# MEMORY.net
KiCad netlist of a schematic drawn in Altium Designer
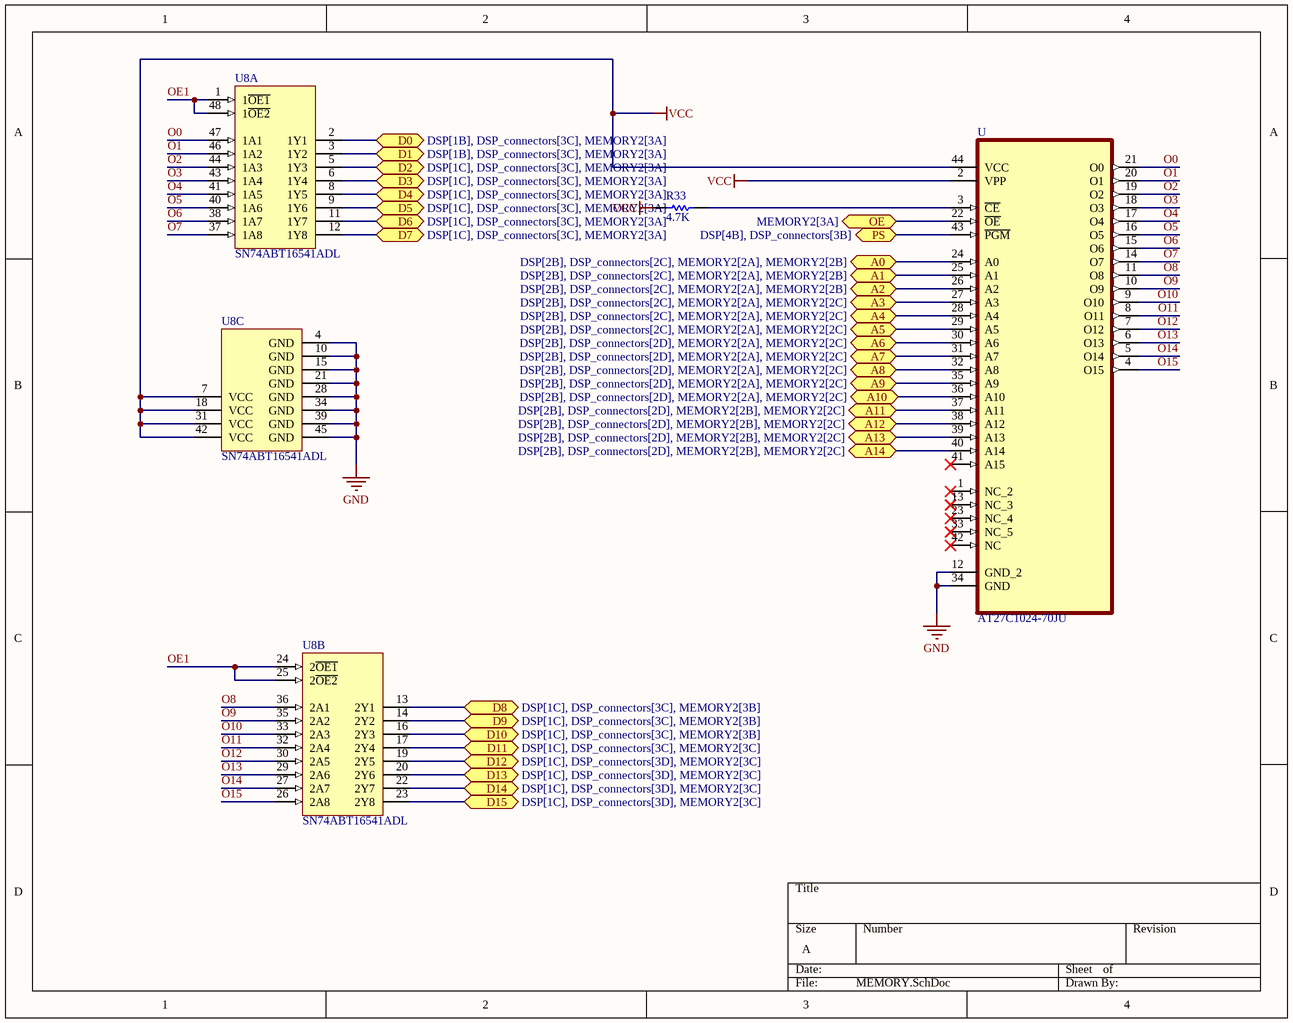
[diagram p0: MEMORY.SchDoc]

(export (version "E")
  (design (tool "Eeschema 10.0.6"))
  (components
    (comp (ref "R33")
      (value "4.7K")
      (footprint "RESC2013X60X35ML10T20")
      (fields (field (name "TOLERANCE") "5%") (field (name "MANUFACTURER") "Yageo"))
      (libsource (lib "Altium Content Vault") (part "RES-2"))
    )
    (comp (ref "U")
      (value "AT27C1024-70JU")
      (footprint "PLCC127P1752X1752X457-44N")
      (description "EPROM - OTP Memory IC 1Mb _64K x 16_ Parallel 70ns 44-PLCC _16.6x16.6_")
      (fields (field (name "MF") "Microchip"))
      (libsource (lib "AT27C1024-70JU") (part "AT27C1024-70JU"))
    )
    (comp (ref "U8")
      (value "SN74ABT16541ADL")
      (footprint "DL0048A_L")
      (description "16-Bit Buffers/Drivers With 3-State Outputs, DL0048A, TUBE")
      (fields
        (field (name "GENERIC PART NUMBER") "SN74ABT16541A")
        (field (name "MANUFACTURER") "Texas Instruments")
      )
      (libsource (lib "Altium Content Vault") (part "TI-74ACT_SN74XX16541X-48"))
    )
  )
  (nets
    (net (code "1") (name "/A0") (class "Default")
      (node (ref "U") (pin "24") (pinfunction "A0_24") (pintype "input"))
    )
    (net (code "2") (name "/A1") (class "Default")
      (node (ref "U") (pin "25") (pinfunction "A1_25") (pintype "input"))
    )
    (net (code "3") (name "/A2") (class "Default")
      (node (ref "U") (pin "26") (pinfunction "A2_26") (pintype "input"))
    )
    (net (code "4") (name "/A3") (class "Default")
      (node (ref "U") (pin "27") (pinfunction "A3_27") (pintype "input"))
    )
    (net (code "5") (name "/A4") (class "Default")
      (node (ref "U") (pin "28") (pinfunction "A4_28") (pintype "input"))
    )
    (net (code "6") (name "/A5") (class "Default")
      (node (ref "U") (pin "29") (pinfunction "A5_29") (pintype "input"))
    )
    (net (code "7") (name "/A6") (class "Default")
      (node (ref "U") (pin "30") (pinfunction "A6_30") (pintype "input"))
    )
    (net (code "8") (name "/A7") (class "Default")
      (node (ref "U") (pin "31") (pinfunction "A7_31") (pintype "input"))
    )
    (net (code "9") (name "/A8") (class "Default")
      (node (ref "U") (pin "32") (pinfunction "A8_32") (pintype "input"))
    )
    (net (code "10") (name "/A9") (class "Default")
      (node (ref "U") (pin "35") (pinfunction "A9_35") (pintype "input"))
    )
    (net (code "11") (name "/A10") (class "Default")
      (node (ref "U") (pin "36") (pinfunction "A10_36") (pintype "input"))
    )
    (net (code "12") (name "/A11") (class "Default")
      (node (ref "U") (pin "37") (pinfunction "A11_37") (pintype "input"))
    )
    (net (code "13") (name "/A12") (class "Default")
      (node (ref "U") (pin "38") (pinfunction "A12_38") (pintype "input"))
    )
    (net (code "14") (name "/A13") (class "Default")
      (node (ref "U") (pin "39") (pinfunction "A13_39") (pintype "input"))
    )
    (net (code "15") (name "/A14") (class "Default")
      (node (ref "U") (pin "40") (pinfunction "A14_40") (pintype "input"))
    )
    (net (code "16") (name "/D0") (class "Default")
      (node (ref "U8") (pin "2") (pinfunction "1Y1_2") (pintype "tri_state"))
    )
    (net (code "17") (name "/D1") (class "Default")
      (node (ref "U8") (pin "3") (pinfunction "1Y2_3") (pintype "tri_state"))
    )
    (net (code "18") (name "/D2") (class "Default")
      (node (ref "U8") (pin "5") (pinfunction "1Y3_5") (pintype "tri_state"))
    )
    (net (code "19") (name "/D3") (class "Default")
      (node (ref "U8") (pin "6") (pinfunction "1Y4_6") (pintype "tri_state"))
    )
    (net (code "20") (name "/D4") (class "Default")
      (node (ref "U8") (pin "8") (pinfunction "1Y5_8") (pintype "tri_state"))
    )
    (net (code "21") (name "/D5") (class "Default")
      (node (ref "U8") (pin "9") (pinfunction "1Y6_9") (pintype "tri_state"))
    )
    (net (code "22") (name "/D6") (class "Default")
      (node (ref "U8") (pin "11") (pinfunction "1Y7_11") (pintype "tri_state"))
    )
    (net (code "23") (name "/D7") (class "Default")
      (node (ref "U8") (pin "12") (pinfunction "1Y8_12") (pintype "tri_state"))
    )
    (net (code "24") (name "/D8") (class "Default")
      (node (ref "U8") (pin "13") (pinfunction "2Y1_13") (pintype "tri_state"))
    )
    (net (code "25") (name "/D9") (class "Default")
      (node (ref "U8") (pin "14") (pinfunction "2Y2_14") (pintype "tri_state"))
    )
    (net (code "26") (name "/D10") (class "Default")
      (node (ref "U8") (pin "16") (pinfunction "2Y3_16") (pintype "tri_state"))
    )
    (net (code "27") (name "/D11") (class "Default")
      (node (ref "U8") (pin "17") (pinfunction "2Y4_17") (pintype "tri_state"))
    )
    (net (code "28") (name "/D12") (class "Default")
      (node (ref "U8") (pin "19") (pinfunction "2Y5_19") (pintype "tri_state"))
    )
    (net (code "29") (name "/D13") (class "Default")
      (node (ref "U8") (pin "20") (pinfunction "2Y6_20") (pintype "tri_state"))
    )
    (net (code "30") (name "/D14") (class "Default")
      (node (ref "U8") (pin "22") (pinfunction "2Y7_22") (pintype "tri_state"))
    )
    (net (code "31") (name "/D15") (class "Default")
      (node (ref "U8") (pin "23") (pinfunction "2Y8_23") (pintype "tri_state"))
    )
    (net (code "32") (name "/O0") (class "Default")
      (node (ref "U") (pin "21") (pinfunction "O0_21") (pintype "output"))
      (node (ref "U8") (pin "47") (pinfunction "1A1_47") (pintype "input"))
    )
    (net (code "33") (name "/O1") (class "Default")
      (node (ref "U") (pin "20") (pinfunction "O1_20") (pintype "output"))
      (node (ref "U8") (pin "46") (pinfunction "1A2_46") (pintype "input"))
    )
    (net (code "34") (name "/O2") (class "Default")
      (node (ref "U") (pin "19") (pinfunction "O2_19") (pintype "output"))
      (node (ref "U8") (pin "44") (pinfunction "1A3_44") (pintype "input"))
    )
    (net (code "35") (name "/O3") (class "Default")
      (node (ref "U") (pin "18") (pinfunction "O3_18") (pintype "output"))
      (node (ref "U8") (pin "43") (pinfunction "1A4_43") (pintype "input"))
    )
    (net (code "36") (name "/O4") (class "Default")
      (node (ref "U") (pin "17") (pinfunction "O4_17") (pintype "output"))
      (node (ref "U8") (pin "41") (pinfunction "1A5_41") (pintype "input"))
    )
    (net (code "37") (name "/O5") (class "Default")
      (node (ref "U") (pin "16") (pinfunction "O5_16") (pintype "output"))
      (node (ref "U8") (pin "40") (pinfunction "1A6_40") (pintype "input"))
    )
    (net (code "38") (name "/O6") (class "Default")
      (node (ref "U") (pin "15") (pinfunction "O6_15") (pintype "output"))
      (node (ref "U8") (pin "38") (pinfunction "1A7_38") (pintype "input"))
    )
    (net (code "39") (name "/O7") (class "Default")
      (node (ref "U") (pin "14") (pinfunction "O7_14") (pintype "output"))
      (node (ref "U8") (pin "37") (pinfunction "1A8_37") (pintype "input"))
    )
    (net (code "40") (name "/O8") (class "Default")
      (node (ref "U") (pin "11") (pinfunction "O8_11") (pintype "output"))
      (node (ref "U8") (pin "36") (pinfunction "2A1_36") (pintype "input"))
    )
    (net (code "41") (name "/O9") (class "Default")
      (node (ref "U") (pin "10") (pinfunction "O9_10") (pintype "output"))
      (node (ref "U8") (pin "35") (pinfunction "2A2_35") (pintype "input"))
    )
    (net (code "42") (name "/O10") (class "Default")
      (node (ref "U") (pin "9") (pinfunction "O10_9") (pintype "output"))
      (node (ref "U8") (pin "33") (pinfunction "2A3_33") (pintype "input"))
    )
    (net (code "43") (name "/O11") (class "Default")
      (node (ref "U") (pin "8") (pinfunction "O11_8") (pintype "output"))
      (node (ref "U8") (pin "32") (pinfunction "2A4_32") (pintype "input"))
    )
    (net (code "44") (name "/O12") (class "Default")
      (node (ref "U") (pin "7") (pinfunction "O12_7") (pintype "output"))
      (node (ref "U8") (pin "30") (pinfunction "2A5_30") (pintype "input"))
    )
    (net (code "45") (name "/O13") (class "Default")
      (node (ref "U") (pin "6") (pinfunction "O13_6") (pintype "output"))
      (node (ref "U8") (pin "29") (pinfunction "2A6_29") (pintype "input"))
    )
    (net (code "46") (name "/O14") (class "Default")
      (node (ref "U") (pin "5") (pinfunction "O14_5") (pintype "output"))
      (node (ref "U8") (pin "27") (pinfunction "2A7_27") (pintype "input"))
    )
    (net (code "47") (name "/O15") (class "Default")
      (node (ref "U") (pin "4") (pinfunction "O15_4") (pintype "output"))
      (node (ref "U8") (pin "26") (pinfunction "2A8_26") (pintype "input"))
    )
    (net (code "48") (name "/OE") (class "Default")
      (node (ref "U") (pin "22") (pinfunction "~{OE}_22") (pintype "input"))
    )
    (net (code "49") (name "/OE1") (class "Default")
      (node (ref "U8") (pin "1") (pinfunction "1~{OE1}_1") (pintype "input"))
      (node (ref "U8") (pin "24") (pinfunction "2~{OE1}_24") (pintype "input"))
      (node (ref "U8") (pin "25") (pinfunction "2~{OE2}_25") (pintype "input"))
      (node (ref "U8") (pin "48") (pinfunction "1~{OE2}_48") (pintype "input"))
    )
    (net (code "50") (name "/PS") (class "Default")
      (node (ref "U") (pin "43") (pinfunction "~{PGM}_43") (pintype "input"))
    )
    (net (code "51") (name "GND") (class "Default")
      (node (ref "U") (pin "12") (pinfunction "GND_2_12") (pintype "passive"))
      (node (ref "U") (pin "34") (pinfunction "GND_34") (pintype "passive"))
      (node (ref "U8") (pin "10") (pinfunction "GND_10") (pintype "power_in"))
      (node (ref "U8") (pin "15") (pinfunction "GND_15") (pintype "power_in"))
      (node (ref "U8") (pin "21") (pinfunction "GND_21") (pintype "power_in"))
      (node (ref "U8") (pin "28") (pinfunction "GND_28") (pintype "power_in"))
      (node (ref "U8") (pin "34") (pinfunction "GND_34") (pintype "power_in"))
      (node (ref "U8") (pin "39") (pinfunction "GND_39") (pintype "power_in"))
      (node (ref "U8") (pin "4") (pinfunction "GND_4") (pintype "power_in"))
      (node (ref "U8") (pin "45") (pinfunction "GND_45") (pintype "power_in"))
    )
    (net (code "52") (name "Net-(U-~{CE})") (class "Default")
      (node (ref "R33") (pin "2") (pinfunction "2_2") (pintype "passive"))
      (node (ref "U") (pin "3") (pinfunction "~{CE}_3") (pintype "input"))
    )
    (net (code "53") (name "VCC") (class "Default")
      (node (ref "R33") (pin "1") (pinfunction "1_1") (pintype "passive"))
      (node (ref "U") (pin "2") (pinfunction "VPP_2") (pintype "power_in"))
      (node (ref "U") (pin "44") (pinfunction "VCC_44") (pintype "power_in"))
      (node (ref "U8") (pin "18") (pinfunction "VCC_18") (pintype "power_in"))
      (node (ref "U8") (pin "31") (pinfunction "VCC_31") (pintype "power_in"))
      (node (ref "U8") (pin "42") (pinfunction "VCC_42") (pintype "power_in"))
      (node (ref "U8") (pin "7") (pinfunction "VCC_7") (pintype "power_in"))
    )
    (net (code "54") (name "unconnected-(U-A15-Pad41)") (class "Default")
      (node (ref "U") (pin "41") (pinfunction "A15_41") (pintype "input+no_connect"))
    )
    (net (code "55") (name "unconnected-(U-NC-Pad42)") (class "Default")
      (node (ref "U") (pin "42") (pinfunction "NC_42") (pintype "input+no_connect"))
    )
    (net (code "56") (name "unconnected-(U-NC_2-Pad1)") (class "Default")
      (node (ref "U") (pin "1") (pinfunction "NC_2_1") (pintype "input+no_connect"))
    )
    (net (code "57") (name "unconnected-(U-NC_3-Pad13)") (class "Default")
      (node (ref "U") (pin "13") (pinfunction "NC_3_13") (pintype "input+no_connect"))
    )
    (net (code "58") (name "unconnected-(U-NC_4-Pad23)") (class "Default")
      (node (ref "U") (pin "23") (pinfunction "NC_4_23") (pintype "input+no_connect"))
    )
    (net (code "59") (name "unconnected-(U-NC_5-Pad33)") (class "Default")
      (node (ref "U") (pin "33") (pinfunction "NC_5_33") (pintype "input+no_connect"))
    )
  )
)
